# DRV8818.net
KiCad netlist of a schematic drawn in EAGLE
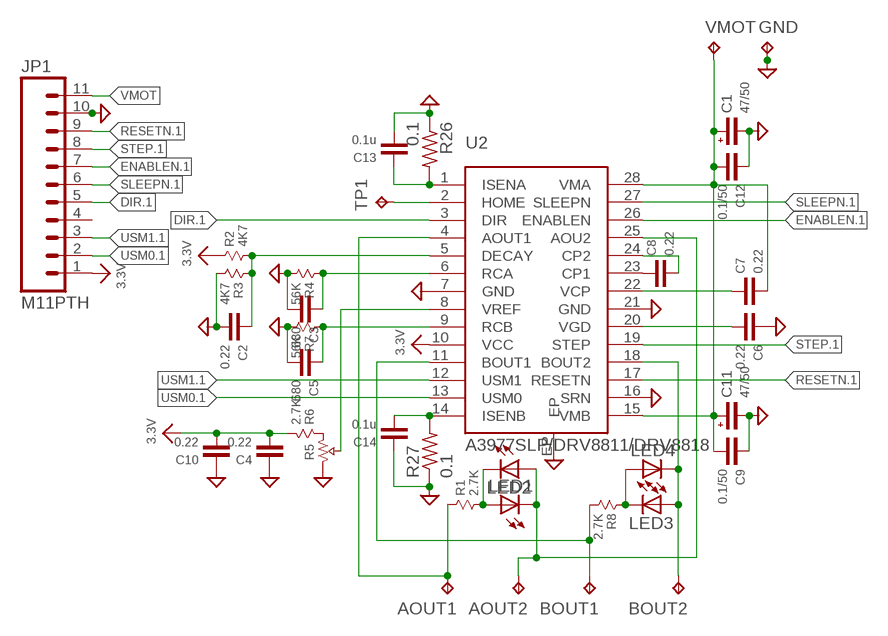
[diagram p0: schematic, sheet 1]

(export (version "E")
  (design (tool "Eeschema 10.0.6"))
  (components
    (comp (ref "AOUT1")
      (value "TPTP20R")
      (footprint "eagle-import:TP20R")
      (libsource (lib "eagle-import") (part "TPTP20R"))
    )
    (comp (ref "AOUT2")
      (value "TPTP20R")
      (footprint "eagle-import:TP20R")
      (libsource (lib "eagle-import") (part "TPTP20R"))
    )
    (comp (ref "BOUT1")
      (value "TPTP20R")
      (footprint "eagle-import:TP20R")
      (libsource (lib "eagle-import") (part "TPTP20R"))
    )
    (comp (ref "BOUT2")
      (value "TPTP20R")
      (footprint "eagle-import:TP20R")
      (libsource (lib "eagle-import") (part "TPTP20R"))
    )
    (comp (ref "C1")
      (value "47/50")
      (footprint "eagle-import:CT7343")
      (libsource (lib "eagle-import") (part "CAP-POL-7343"))
    )
    (comp (ref "C2")
      (value "0.22")
      (footprint "eagle-import:0603")
      (libsource (lib "eagle-import") (part "CAP-0603"))
    )
    (comp (ref "C3")
      (value "680")
      (footprint "eagle-import:0603")
      (libsource (lib "eagle-import") (part "CAP-0603"))
    )
    (comp (ref "C4")
      (value "0.22")
      (footprint "eagle-import:0603")
      (libsource (lib "eagle-import") (part "CAP-0603"))
    )
    (comp (ref "C5")
      (value "680")
      (footprint "eagle-import:0603")
      (libsource (lib "eagle-import") (part "CAP-0603"))
    )
    (comp (ref "C6")
      (value "0.22")
      (footprint "eagle-import:0603")
      (libsource (lib "eagle-import") (part "CAP-0603"))
    )
    (comp (ref "C7")
      (value "0.22")
      (footprint "eagle-import:0603")
      (libsource (lib "eagle-import") (part "CAP-0603"))
    )
    (comp (ref "C8")
      (value "0.22")
      (footprint "eagle-import:0603")
      (libsource (lib "eagle-import") (part "CAP-0603"))
    )
    (comp (ref "C9")
      (value "0.1/50")
      (footprint "eagle-import:0603")
      (libsource (lib "eagle-import") (part "CAP-0603"))
    )
    (comp (ref "C10")
      (value "0.22")
      (footprint "eagle-import:0603")
      (libsource (lib "eagle-import") (part "CAP-0603"))
    )
    (comp (ref "C11")
      (value "47/50")
      (footprint "eagle-import:CT7343")
      (libsource (lib "eagle-import") (part "CAP-POL-7343"))
    )
    (comp (ref "C12")
      (value "0.1/50")
      (footprint "eagle-import:0603")
      (libsource (lib "eagle-import") (part "CAP-0603"))
    )
    (comp (ref "C13")
      (value "0.1u")
      (footprint "eagle-import:0603")
      (libsource (lib "eagle-import") (part "CAP-0603"))
    )
    (comp (ref "C14")
      (value "0.1u")
      (footprint "eagle-import:0603")
      (libsource (lib "eagle-import") (part "CAP-0603"))
    )
    (comp (ref "GND")
      (value "TPTP20R")
      (footprint "eagle-import:TP20R")
      (libsource (lib "eagle-import") (part "TPTP20R"))
    )
    (comp (ref "JP1")
      (value "M11PTH")
      (footprint "eagle-import:1X11")
      (libsource (lib "eagle-import") (part "M11PTH"))
    )
    (comp (ref "LED1")
      (value "LEDCHIP-LED0603")
      (footprint "eagle-import:CHIP-LED0603")
      (libsource (lib "eagle-import") (part "LEDCHIP-LED0603"))
    )
    (comp (ref "LED2")
      (value "LEDCHIP-LED0603")
      (footprint "eagle-import:CHIP-LED0603")
      (libsource (lib "eagle-import") (part "LEDCHIP-LED0603"))
    )
    (comp (ref "LED3")
      (value "LEDCHIP-LED0603")
      (footprint "eagle-import:CHIP-LED0603")
      (libsource (lib "eagle-import") (part "LEDCHIP-LED0603"))
    )
    (comp (ref "LED4")
      (value "LEDCHIP-LED0603")
      (footprint "eagle-import:CHIP-LED0603")
      (libsource (lib "eagle-import") (part "LEDCHIP-LED0603"))
    )
    (comp (ref "R1")
      (value "2.7K")
      (footprint "eagle-import:0603")
      (libsource (lib "eagle-import") (part "RESISTOR-0603"))
    )
    (comp (ref "R2")
      (value "4K7")
      (footprint "eagle-import:0603")
      (libsource (lib "eagle-import") (part "RESISTOR-0603"))
    )
    (comp (ref "R3")
      (value "4K7")
      (footprint "eagle-import:0603")
      (libsource (lib "eagle-import") (part "RESISTOR-0603"))
    )
    (comp (ref "R4")
      (value "56K")
      (footprint "eagle-import:0603")
      (libsource (lib "eagle-import") (part "RESISTOR-0603"))
    )
    (comp (ref "R5")
      (value "PVZ3A")
      (footprint "eagle-import:PVZ3A")
      (libsource (lib "eagle-import") (part "PVZ3A"))
    )
    (comp (ref "R6")
      (value "2.7K")
      (footprint "eagle-import:0603")
      (libsource (lib "eagle-import") (part "RESISTOR-0603"))
    )
    (comp (ref "R7")
      (value "56K")
      (footprint "eagle-import:0603")
      (libsource (lib "eagle-import") (part "RESISTOR-0603"))
    )
    (comp (ref "R8")
      (value "2.7K")
      (footprint "eagle-import:0603")
      (libsource (lib "eagle-import") (part "RESISTOR-0603"))
    )
    (comp (ref "R26")
      (value "0.1")
      (footprint "eagle-import:R2512")
      (libsource (lib "eagle-import") (part "R-US_R2512"))
    )
    (comp (ref "R27")
      (value "0.1")
      (footprint "eagle-import:R2512")
      (libsource (lib "eagle-import") (part "R-US_R2512"))
    )
    (comp (ref "TP1")
      (value "TPTP08R")
      (footprint "eagle-import:TP08R")
      (libsource (lib "eagle-import") (part "TPTP08R"))
    )
    (comp (ref "U2")
      (value "A3977SLP/DRV8811/DRV8818")
      (footprint "eagle-import:SSOP28EP")
      (libsource (lib "eagle-import") (part "DRV8811"))
    )
    (comp (ref "VMOT")
      (value "TPTP20R")
      (footprint "eagle-import:TP20R")
      (libsource (lib "eagle-import") (part "TPTP20R"))
    )
  )
  (nets
    (net (code "1") (name "3.3V") (class "Default")
      (node (ref "C10") (pin "1") (pinfunction "1_1") (pintype "passive"))
      (node (ref "C4") (pin "1") (pinfunction "1_1") (pintype "passive"))
      (node (ref "JP1") (pin "1") (pinfunction "1_1") (pintype "passive"))
      (node (ref "R2") (pin "1") (pinfunction "1_1") (pintype "passive"))
      (node (ref "R6") (pin "2") (pinfunction "2_2") (pintype "passive"))
      (node (ref "U2") (pin "10") (pinfunction "VCC_10") (pintype "bidirectional"))
    )
    (net (code "2") (name "DIR.1") (class "Default")
      (node (ref "JP1") (pin "5") (pinfunction "5_5") (pintype "passive"))
      (node (ref "U2") (pin "3") (pinfunction "DIR_3") (pintype "bidirectional"))
    )
    (net (code "3") (name "ENABLEN.1") (class "Default")
      (node (ref "JP1") (pin "7") (pinfunction "7_7") (pintype "passive"))
      (node (ref "U2") (pin "26") (pinfunction "ENABLEN_26") (pintype "bidirectional"))
    )
    (net (code "4") (name "GND") (class "Default")
      (node (ref "C1") (pin "-") (pinfunction "-_-") (pintype "passive"))
      (node (ref "C10") (pin "2") (pinfunction "2_2") (pintype "passive"))
      (node (ref "C11") (pin "-") (pinfunction "-_-") (pintype "passive"))
      (node (ref "C12") (pin "2") (pinfunction "2_2") (pintype "passive"))
      (node (ref "C13") (pin "1") (pinfunction "1_1") (pintype "passive"))
      (node (ref "C14") (pin "2") (pinfunction "2_2") (pintype "passive"))
      (node (ref "C2") (pin "1") (pinfunction "1_1") (pintype "passive"))
      (node (ref "C3") (pin "1") (pinfunction "1_1") (pintype "passive"))
      (node (ref "C4") (pin "2") (pinfunction "2_2") (pintype "passive"))
      (node (ref "C5") (pin "1") (pinfunction "1_1") (pintype "passive"))
      (node (ref "C6") (pin "2") (pinfunction "2_2") (pintype "passive"))
      (node (ref "C9") (pin "2") (pinfunction "2_2") (pintype "passive"))
      (node (ref "GND") (pin "TP") (pinfunction "TP_TP") (pintype "input"))
      (node (ref "JP1") (pin "10") (pinfunction "10_10") (pintype "passive"))
      (node (ref "R26") (pin "1") (pinfunction "1_1") (pintype "passive"))
      (node (ref "R27") (pin "1") (pinfunction "1_1") (pintype "passive"))
      (node (ref "R3") (pin "2") (pinfunction "2_2") (pintype "passive"))
      (node (ref "R4") (pin "2") (pinfunction "2_2") (pintype "passive"))
      (node (ref "R5") (pin "1") (pinfunction "1_1") (pintype "passive"))
      (node (ref "R7") (pin "2") (pinfunction "2_2") (pintype "passive"))
      (node (ref "U2") (pin "16") (pinfunction "SRN_16") (pintype "bidirectional"))
      (node (ref "U2") (pin "21") (pinfunction "GND_21") (pintype "power_in"))
      (node (ref "U2") (pin "7") (pinfunction "GND_7") (pintype "power_in"))
      (node (ref "U2") (pin "EP") (pinfunction "EP_EP") (pintype "bidirectional"))
    )
    (net (code "5") (name "Net-(LED1-PadA)") (class "Default")
      (node (ref "LED1") (pin "A") (pinfunction "A_A") (pintype "passive"))
      (node (ref "LED2") (pin "C") (pinfunction "C_C") (pintype "passive"))
      (node (ref "R1") (pin "2") (pinfunction "2_2") (pintype "passive"))
    )
    (net (code "6") (name "Net-(LED3-PadC)") (class "Default")
      (node (ref "LED3") (pin "C") (pinfunction "C_C") (pintype "passive"))
      (node (ref "LED4") (pin "A") (pinfunction "A_A") (pintype "passive"))
      (node (ref "R8") (pin "1") (pinfunction "1_1") (pintype "passive"))
    )
    (net (code "7") (name "Net-(R5-Pad3)") (class "Default")
      (node (ref "R5") (pin "3") (pinfunction "3_3") (pintype "passive"))
      (node (ref "R6") (pin "1") (pinfunction "1_1") (pintype "passive"))
    )
    (net (code "8") (name "Net-(U2-AOU2)") (class "Default")
      (node (ref "AOUT2") (pin "TP") (pinfunction "TP_TP") (pintype "input"))
      (node (ref "LED1") (pin "C") (pinfunction "C_C") (pintype "passive"))
      (node (ref "LED2") (pin "A") (pinfunction "A_A") (pintype "passive"))
      (node (ref "U2") (pin "25") (pinfunction "AOU2_25") (pintype "bidirectional"))
    )
    (net (code "9") (name "Net-(U2-AOUT1)") (class "Default")
      (node (ref "AOUT1") (pin "TP") (pinfunction "TP_TP") (pintype "input"))
      (node (ref "R1") (pin "1") (pinfunction "1_1") (pintype "passive"))
      (node (ref "U2") (pin "4") (pinfunction "AOUT1_4") (pintype "bidirectional"))
    )
    (net (code "10") (name "Net-(U2-BOUT1)") (class "Default")
      (node (ref "BOUT1") (pin "TP") (pinfunction "TP_TP") (pintype "input"))
      (node (ref "R8") (pin "2") (pinfunction "2_2") (pintype "passive"))
      (node (ref "U2") (pin "11") (pinfunction "BOUT1_11") (pintype "bidirectional"))
    )
    (net (code "11") (name "Net-(U2-BOUT2)") (class "Default")
      (node (ref "BOUT2") (pin "TP") (pinfunction "TP_TP") (pintype "input"))
      (node (ref "LED3") (pin "A") (pinfunction "A_A") (pintype "passive"))
      (node (ref "LED4") (pin "C") (pinfunction "C_C") (pintype "passive"))
      (node (ref "U2") (pin "18") (pinfunction "BOUT2_18") (pintype "bidirectional"))
    )
    (net (code "12") (name "Net-(U2-CP1)") (class "Default")
      (node (ref "C8") (pin "2") (pinfunction "2_2") (pintype "passive"))
      (node (ref "U2") (pin "23") (pinfunction "CP1_23") (pintype "bidirectional"))
    )
    (net (code "13") (name "Net-(U2-CP2)") (class "Default")
      (node (ref "C8") (pin "1") (pinfunction "1_1") (pintype "passive"))
      (node (ref "U2") (pin "24") (pinfunction "CP2_24") (pintype "bidirectional"))
    )
    (net (code "14") (name "Net-(U2-DECAY)") (class "Default")
      (node (ref "C2") (pin "2") (pinfunction "2_2") (pintype "passive"))
      (node (ref "R2") (pin "2") (pinfunction "2_2") (pintype "passive"))
      (node (ref "R3") (pin "1") (pinfunction "1_1") (pintype "passive"))
      (node (ref "U2") (pin "5") (pinfunction "DECAY_5") (pintype "bidirectional"))
    )
    (net (code "15") (name "Net-(U2-HOME)") (class "Default")
      (node (ref "TP1") (pin "TP") (pinfunction "TP_TP") (pintype "input"))
      (node (ref "U2") (pin "2") (pinfunction "HOME_2") (pintype "bidirectional"))
    )
    (net (code "16") (name "Net-(U2-ISENA)") (class "Default")
      (node (ref "C13") (pin "2") (pinfunction "2_2") (pintype "passive"))
      (node (ref "R26") (pin "2") (pinfunction "2_2") (pintype "passive"))
      (node (ref "U2") (pin "1") (pinfunction "ISENA_1") (pintype "bidirectional"))
    )
    (net (code "17") (name "Net-(U2-ISENB)") (class "Default")
      (node (ref "C14") (pin "1") (pinfunction "1_1") (pintype "passive"))
      (node (ref "R27") (pin "2") (pinfunction "2_2") (pintype "passive"))
      (node (ref "U2") (pin "14") (pinfunction "ISENB_14") (pintype "bidirectional"))
    )
    (net (code "18") (name "Net-(U2-RCA)") (class "Default")
      (node (ref "C3") (pin "2") (pinfunction "2_2") (pintype "passive"))
      (node (ref "R4") (pin "1") (pinfunction "1_1") (pintype "passive"))
      (node (ref "U2") (pin "6") (pinfunction "RCA_6") (pintype "bidirectional"))
    )
    (net (code "19") (name "Net-(U2-RCB)") (class "Default")
      (node (ref "C5") (pin "2") (pinfunction "2_2") (pintype "passive"))
      (node (ref "R7") (pin "1") (pinfunction "1_1") (pintype "passive"))
      (node (ref "U2") (pin "9") (pinfunction "RCB_9") (pintype "bidirectional"))
    )
    (net (code "20") (name "Net-(U2-VCP)") (class "Default")
      (node (ref "C7") (pin "2") (pinfunction "2_2") (pintype "passive"))
      (node (ref "U2") (pin "22") (pinfunction "VCP_22") (pintype "bidirectional"))
    )
    (net (code "21") (name "Net-(U2-VGD)") (class "Default")
      (node (ref "C6") (pin "1") (pinfunction "1_1") (pintype "passive"))
      (node (ref "U2") (pin "20") (pinfunction "VGD_20") (pintype "bidirectional"))
    )
    (net (code "22") (name "Net-(U2-VREF)") (class "Default")
      (node (ref "R5") (pin "2") (pinfunction "2_2") (pintype "passive"))
      (node (ref "U2") (pin "8") (pinfunction "VREF_8") (pintype "bidirectional"))
    )
    (net (code "23") (name "RESETN.1") (class "Default")
      (node (ref "JP1") (pin "9") (pinfunction "9_9") (pintype "passive"))
      (node (ref "U2") (pin "17") (pinfunction "RESETN_17") (pintype "bidirectional"))
    )
    (net (code "24") (name "SLEEPN.1") (class "Default")
      (node (ref "JP1") (pin "6") (pinfunction "6_6") (pintype "passive"))
      (node (ref "U2") (pin "27") (pinfunction "SLEEPN_27") (pintype "bidirectional"))
    )
    (net (code "25") (name "STEP.1") (class "Default")
      (node (ref "JP1") (pin "8") (pinfunction "8_8") (pintype "passive"))
      (node (ref "U2") (pin "19") (pinfunction "STEP_19") (pintype "bidirectional"))
    )
    (net (code "26") (name "USM0.1") (class "Default")
      (node (ref "JP1") (pin "2") (pinfunction "2_2") (pintype "passive"))
      (node (ref "U2") (pin "13") (pinfunction "USM0_13") (pintype "bidirectional"))
    )
    (net (code "27") (name "USM1.1") (class "Default")
      (node (ref "JP1") (pin "3") (pinfunction "3_3") (pintype "passive"))
      (node (ref "U2") (pin "12") (pinfunction "USM1_12") (pintype "bidirectional"))
    )
    (net (code "28") (name "VMOT") (class "Default")
      (node (ref "C1") (pin "+") (pinfunction "+_+") (pintype "passive"))
      (node (ref "C11") (pin "+") (pinfunction "+_+") (pintype "passive"))
      (node (ref "C12") (pin "1") (pinfunction "1_1") (pintype "passive"))
      (node (ref "C7") (pin "1") (pinfunction "1_1") (pintype "passive"))
      (node (ref "C9") (pin "1") (pinfunction "1_1") (pintype "passive"))
      (node (ref "JP1") (pin "11") (pinfunction "11_11") (pintype "passive"))
      (node (ref "U2") (pin "15") (pinfunction "VMB_15") (pintype "bidirectional"))
      (node (ref "U2") (pin "28") (pinfunction "VMA_28") (pintype "bidirectional"))
      (node (ref "VMOT") (pin "TP") (pinfunction "TP_TP") (pintype "input"))
    )
    (net (code "29") (name "unconnected-(JP1-Pad4)") (class "Default")
      (node (ref "JP1") (pin "4") (pinfunction "4_4") (pintype "passive"))
    )
  )
)
